# Snickerdoodle_FPGA_JA.net
KiCad netlist of a schematic drawn in Altium Designer
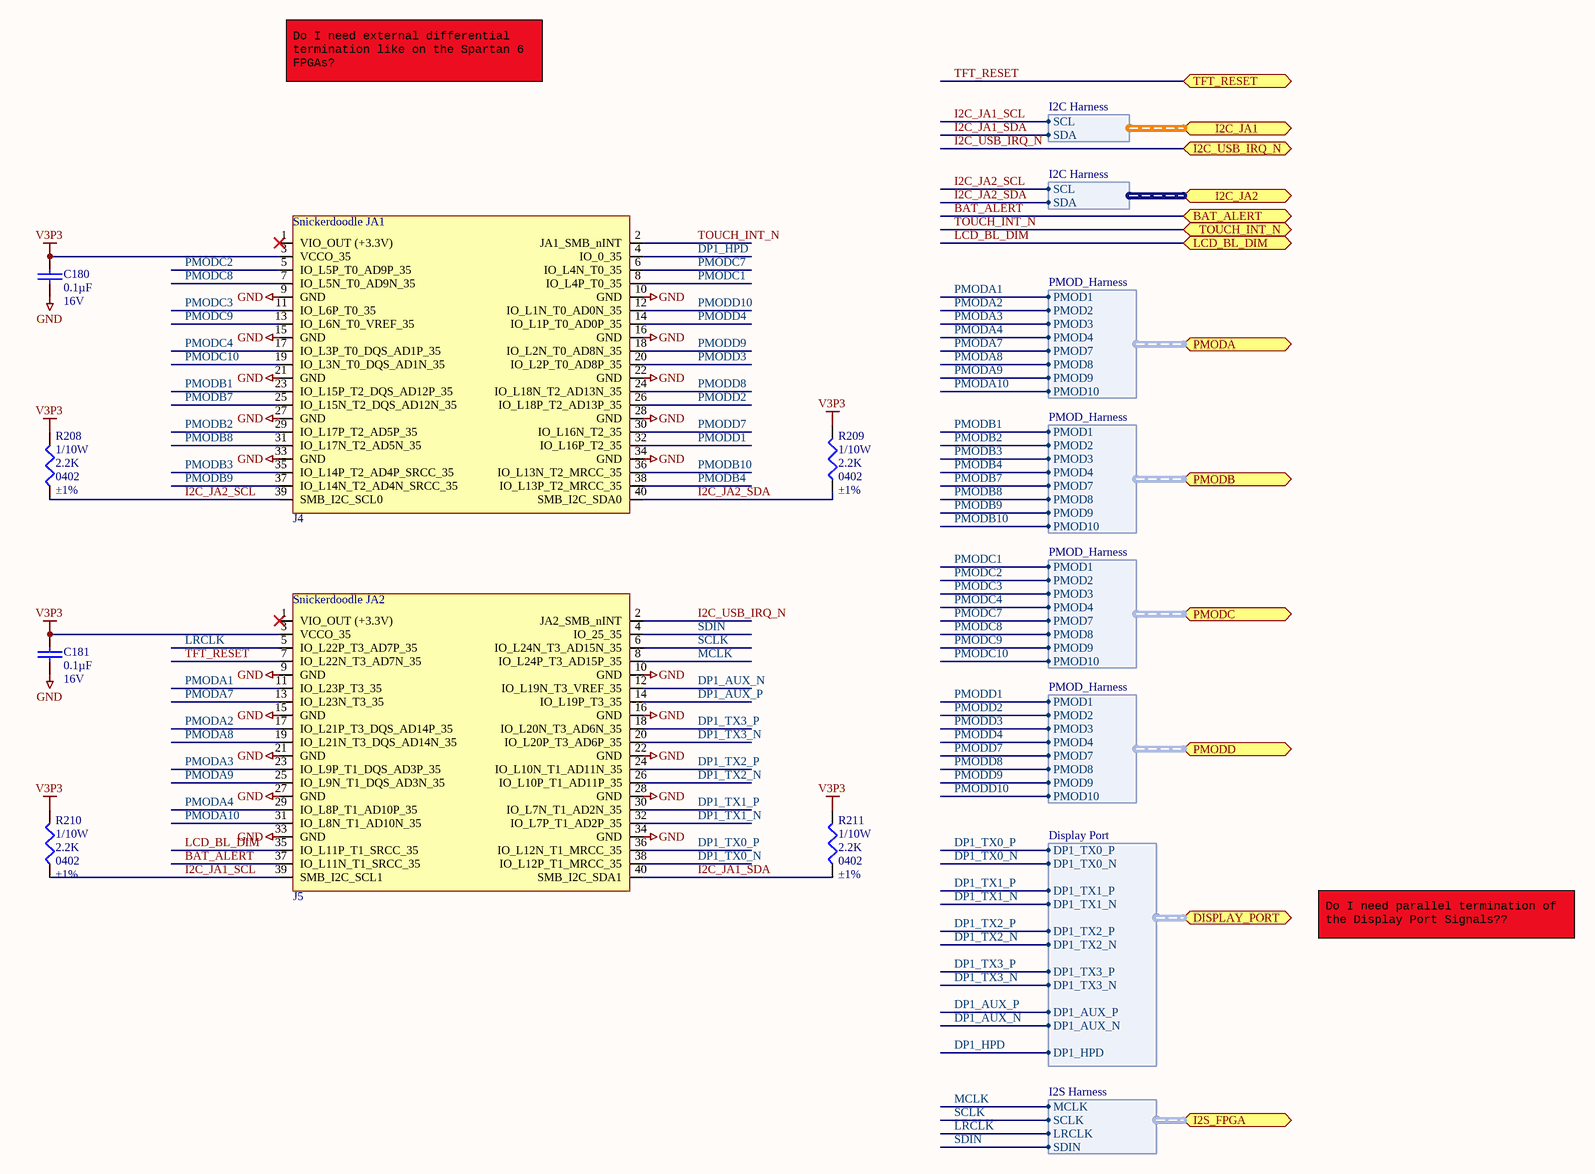
[diagram p0: Snickerdoodle FPGA JA.SchDoc]

(export (version "E")
  (design (tool "Eeschema 10.0.6"))
  (components
    (comp (ref "C180")
      (value "0.1uF")
      (footprint "C_0402")
      (description "CAP CER .10UF 16V X7R 0402")
      (fields
        (field (name "MANUFACTURER") "TDK Corporation")
        (field (name "MANUFACTURER PART NUMBER") "C1005X7R1C104K050BC")
        (field (name "CAPACITANCE") "0.1µF")
        (field (name "VOLTAGE - RATED") "16V")
      )
      (libsource (lib "Main Library") (part "C_0402_0.1UF_16V"))
    )
    (comp (ref "C181")
      (value "0.1uF")
      (footprint "C_0402")
      (description "CAP CER .10UF 16V X7R 0402")
      (fields
        (field (name "MANUFACTURER") "TDK Corporation")
        (field (name "MANUFACTURER PART NUMBER") "C1005X7R1C104K050BC")
        (field (name "CAPACITANCE") "0.1µF")
        (field (name "VOLTAGE - RATED") "16V")
      )
      (libsource (lib "Main Library") (part "C_0402_0.1UF_16V"))
    )
    (comp (ref "J4")
      (value "J_SNICKERDOODLE_JA1")
      (footprint "TFM12001-X-D-A")
      (libsource (lib "Cospan Design") (part "J_SNICKERDOODLE_JA1"))
    )
    (comp (ref "J5")
      (value "J_SNICKERDOODLE_JA2")
      (footprint "TFM12001-X-D-A")
      (libsource (lib "Cospan Design") (part "J_SNICKERDOODLE_JA2"))
    )
    (comp (ref "R208")
      (value "2.2k Ohms")
      (footprint "R_0402")
      (description "RES 2.20K OHM 1/10W 1% 0402 SMD")
      (fields
        (field (name "MANUFACTURER") "Yageo")
        (field (name "MANUFACTURER PART NUMBER") "RC0402FR-072K2L")
        (field (name "POWER (WATTS)") "1/10W")
        (field (name "RESISTANCE IN OHMS") "2.2K")
        (field (name "CASE") "0402")
        (field (name "TOLERANCE") "±1%")
      )
      (libsource (lib "Main Library") (part "R_0402_2.2K"))
    )
    (comp (ref "R209")
      (value "2.2k Ohms")
      (footprint "R_0402")
      (description "RES 2.20K OHM 1/10W 1% 0402 SMD")
      (fields
        (field (name "MANUFACTURER") "Yageo")
        (field (name "MANUFACTURER PART NUMBER") "RC0402FR-072K2L")
        (field (name "POWER (WATTS)") "1/10W")
        (field (name "RESISTANCE IN OHMS") "2.2K")
        (field (name "CASE") "0402")
        (field (name "TOLERANCE") "±1%")
      )
      (libsource (lib "Main Library") (part "R_0402_2.2K"))
    )
    (comp (ref "R210")
      (value "2.2k Ohms")
      (footprint "R_0402")
      (description "RES 2.20K OHM 1/10W 1% 0402 SMD")
      (fields
        (field (name "MANUFACTURER") "Yageo")
        (field (name "MANUFACTURER PART NUMBER") "RC0402FR-072K2L")
        (field (name "POWER (WATTS)") "1/10W")
        (field (name "RESISTANCE IN OHMS") "2.2K")
        (field (name "CASE") "0402")
        (field (name "TOLERANCE") "±1%")
      )
      (libsource (lib "Main Library") (part "R_0402_2.2K"))
    )
    (comp (ref "R211")
      (value "2.2k Ohms")
      (footprint "R_0402")
      (description "RES 2.20K OHM 1/10W 1% 0402 SMD")
      (fields
        (field (name "MANUFACTURER") "Yageo")
        (field (name "MANUFACTURER PART NUMBER") "RC0402FR-072K2L")
        (field (name "POWER (WATTS)") "1/10W")
        (field (name "RESISTANCE IN OHMS") "2.2K")
        (field (name "CASE") "0402")
        (field (name "TOLERANCE") "±1%")
      )
      (libsource (lib "Main Library") (part "R_0402_2.2K"))
    )
  )
  (nets
    (net (code "7") (name "/BAT_ALERT") (class "Default")
      (node (ref "J5") (pin "37") (pinfunction "IO_L11N_T1_SRCC_35_37") (pintype "passive"))
    )
    (net (code "8") (name "/DP1_AUX_N") (class "Default")
      (node (ref "J5") (pin "12") (pinfunction "IO_L19N_T3_VREF_35_12") (pintype "passive"))
    )
    (net (code "9") (name "/DP1_AUX_P") (class "Default")
      (node (ref "J5") (pin "14") (pinfunction "IO_L19P_T3_35_14") (pintype "passive"))
    )
    (net (code "10") (name "/DP1_HPD") (class "Default")
      (node (ref "J4") (pin "4") (pinfunction "IO_0_35_4") (pintype "passive"))
    )
    (net (code "11") (name "/DP1_TX0_N") (class "Default")
      (node (ref "J5") (pin "38") (pinfunction "IO_L12P_T1_MRCC_35_38") (pintype "passive"))
    )
    (net (code "12") (name "/DP1_TX0_P") (class "Default")
      (node (ref "J5") (pin "36") (pinfunction "IO_L12N_T1_MRCC_35_36") (pintype "passive"))
    )
    (net (code "13") (name "/DP1_TX1_N") (class "Default")
      (node (ref "J5") (pin "32") (pinfunction "IO_L7P_T1_AD2P_35_32") (pintype "passive"))
    )
    (net (code "14") (name "/DP1_TX1_P") (class "Default")
      (node (ref "J5") (pin "30") (pinfunction "IO_L7N_T1_AD2N_35_30") (pintype "passive"))
    )
    (net (code "15") (name "/DP1_TX2_N") (class "Default")
      (node (ref "J5") (pin "26") (pinfunction "IO_L10P_T1_AD11P_35_26") (pintype "passive"))
    )
    (net (code "16") (name "/DP1_TX2_P") (class "Default")
      (node (ref "J5") (pin "24") (pinfunction "IO_L10N_T1_AD11N_35_24") (pintype "passive"))
    )
    (net (code "17") (name "/DP1_TX3_N") (class "Default")
      (node (ref "J5") (pin "20") (pinfunction "IO_L20P_T3_AD6P_35_20") (pintype "passive"))
    )
    (net (code "18") (name "/DP1_TX3_P") (class "Default")
      (node (ref "J5") (pin "18") (pinfunction "IO_L20N_T3_AD6N_35_18") (pintype "passive"))
    )
    (net (code "19") (name "/I2C_JA1_SCL") (class "Default")
      (node (ref "J5") (pin "39") (pinfunction "SMB_I2C_SCL1_39") (pintype "passive"))
      (node (ref "R210") (pin "2") (pinfunction "2_2") (pintype "passive"))
    )
    (net (code "20") (name "/I2C_JA1_SDA") (class "Default")
      (node (ref "J5") (pin "40") (pinfunction "SMB_I2C_SDA1_40") (pintype "passive"))
      (node (ref "R211") (pin "2") (pinfunction "2_2") (pintype "passive"))
    )
    (net (code "21") (name "/I2C_JA2_SCL") (class "Default")
      (node (ref "J4") (pin "39") (pinfunction "SMB_I2C_SCL0_39") (pintype "passive"))
      (node (ref "R208") (pin "2") (pinfunction "2_2") (pintype "passive"))
    )
    (net (code "22") (name "/I2C_JA2_SDA") (class "Default")
      (node (ref "J4") (pin "40") (pinfunction "SMB_I2C_SDA0_40") (pintype "passive"))
      (node (ref "R209") (pin "2") (pinfunction "2_2") (pintype "passive"))
    )
    (net (code "23") (name "/I2C_USB_IRQ_N") (class "Default")
      (node (ref "J5") (pin "2") (pinfunction "JA2_SMB_nINT_2") (pintype "passive"))
    )
    (net (code "24") (name "/LCD_BL_DIM") (class "Default")
      (node (ref "J5") (pin "35") (pinfunction "IO_L11P_T1_SRCC_35_35") (pintype "passive"))
    )
    (net (code "25") (name "/LRCLK") (class "Default")
      (node (ref "J5") (pin "5") (pinfunction "IO_L22P_T3_AD7P_35_5") (pintype "passive"))
    )
    (net (code "26") (name "/MCLK") (class "Default")
      (node (ref "J5") (pin "8") (pinfunction "IO_L24P_T3_AD15P_35_8") (pintype "passive"))
    )
    (net (code "27") (name "/PMODA1") (class "Default")
      (node (ref "J5") (pin "11") (pinfunction "IO_L23P_T3_35_11") (pintype "passive"))
    )
    (net (code "28") (name "/PMODA2") (class "Default")
      (node (ref "J5") (pin "17") (pinfunction "IO_L21P_T3_DQS_AD14P_35_17") (pintype "passive"))
    )
    (net (code "29") (name "/PMODA3") (class "Default")
      (node (ref "J5") (pin "23") (pinfunction "IO_L9P_T1_DQS_AD3P_35_23") (pintype "passive"))
    )
    (net (code "30") (name "/PMODA4") (class "Default")
      (node (ref "J5") (pin "29") (pinfunction "IO_L8P_T1_AD10P_35_29") (pintype "passive"))
    )
    (net (code "31") (name "/PMODA7") (class "Default")
      (node (ref "J5") (pin "13") (pinfunction "IO_L23N_T3_35_13") (pintype "passive"))
    )
    (net (code "32") (name "/PMODA8") (class "Default")
      (node (ref "J5") (pin "19") (pinfunction "IO_L21N_T3_DQS_AD14N_35_19") (pintype "passive"))
    )
    (net (code "33") (name "/PMODA9") (class "Default")
      (node (ref "J5") (pin "25") (pinfunction "IO_L9N_T1_DQS_AD3N_35_25") (pintype "passive"))
    )
    (net (code "34") (name "/PMODA10") (class "Default")
      (node (ref "J5") (pin "31") (pinfunction "IO_L8N_T1_AD10N_35_31") (pintype "passive"))
    )
    (net (code "35") (name "/PMODB1") (class "Default")
      (node (ref "J4") (pin "23") (pinfunction "IO_L15P_T2_DQS_AD12P_35_23") (pintype "passive"))
    )
    (net (code "36") (name "/PMODB2") (class "Default")
      (node (ref "J4") (pin "29") (pinfunction "IO_L17P_T2_AD5P_35_29") (pintype "passive"))
    )
    (net (code "37") (name "/PMODB3") (class "Default")
      (node (ref "J4") (pin "35") (pinfunction "IO_L14P_T2_AD4P_SRCC_35_35") (pintype "passive"))
    )
    (net (code "38") (name "/PMODB4") (class "Default")
      (node (ref "J4") (pin "38") (pinfunction "IO_L13P_T2_MRCC_35_38") (pintype "passive"))
    )
    (net (code "39") (name "/PMODB7") (class "Default")
      (node (ref "J4") (pin "25") (pinfunction "IO_L15N_T2_DQS_AD12N_35_25") (pintype "passive"))
    )
    (net (code "40") (name "/PMODB8") (class "Default")
      (node (ref "J4") (pin "31") (pinfunction "IO_L17N_T2_AD5N_35_31") (pintype "passive"))
    )
    (net (code "41") (name "/PMODB9") (class "Default")
      (node (ref "J4") (pin "37") (pinfunction "IO_L14N_T2_AD4N_SRCC_35_37") (pintype "passive"))
    )
    (net (code "42") (name "/PMODB10") (class "Default")
      (node (ref "J4") (pin "36") (pinfunction "IO_L13N_T2_MRCC_35_36") (pintype "passive"))
    )
    (net (code "43") (name "/PMODC1") (class "Default")
      (node (ref "J4") (pin "8") (pinfunction "IO_L4P_T0_35_8") (pintype "passive"))
    )
    (net (code "44") (name "/PMODC2") (class "Default")
      (node (ref "J4") (pin "5") (pinfunction "IO_L5P_T0_AD9P_35_5") (pintype "passive"))
    )
    (net (code "45") (name "/PMODC3") (class "Default")
      (node (ref "J4") (pin "11") (pinfunction "IO_L6P_T0_35_11") (pintype "passive"))
    )
    (net (code "46") (name "/PMODC4") (class "Default")
      (node (ref "J4") (pin "17") (pinfunction "IO_L3P_T0_DQS_AD1P_35_17") (pintype "passive"))
    )
    (net (code "47") (name "/PMODC7") (class "Default")
      (node (ref "J4") (pin "6") (pinfunction "IO_L4N_T0_35_6") (pintype "passive"))
    )
    (net (code "48") (name "/PMODC8") (class "Default")
      (node (ref "J4") (pin "7") (pinfunction "IO_L5N_T0_AD9N_35_7") (pintype "passive"))
    )
    (net (code "49") (name "/PMODC9") (class "Default")
      (node (ref "J4") (pin "13") (pinfunction "IO_L6N_T0_VREF_35_13") (pintype "passive"))
    )
    (net (code "50") (name "/PMODC10") (class "Default")
      (node (ref "J4") (pin "19") (pinfunction "IO_L3N_T0_DQS_AD1N_35_19") (pintype "passive"))
    )
    (net (code "51") (name "/PMODD1") (class "Default")
      (node (ref "J4") (pin "32") (pinfunction "IO_L16P_T2_35_32") (pintype "passive"))
    )
    (net (code "52") (name "/PMODD2") (class "Default")
      (node (ref "J4") (pin "26") (pinfunction "IO_L18P_T2_AD13P_35_26") (pintype "passive"))
    )
    (net (code "53") (name "/PMODD3") (class "Default")
      (node (ref "J4") (pin "20") (pinfunction "IO_L2P_T0_AD8P_35_20") (pintype "passive"))
    )
    (net (code "54") (name "/PMODD4") (class "Default")
      (node (ref "J4") (pin "14") (pinfunction "IO_L1P_T0_AD0P_35_14") (pintype "passive"))
    )
    (net (code "55") (name "/PMODD7") (class "Default")
      (node (ref "J4") (pin "30") (pinfunction "IO_L16N_T2_35_30") (pintype "passive"))
    )
    (net (code "56") (name "/PMODD8") (class "Default")
      (node (ref "J4") (pin "24") (pinfunction "IO_L18N_T2_AD13N_35_24") (pintype "passive"))
    )
    (net (code "57") (name "/PMODD9") (class "Default")
      (node (ref "J4") (pin "18") (pinfunction "IO_L2N_T0_AD8N_35_18") (pintype "passive"))
    )
    (net (code "58") (name "/PMODD10") (class "Default")
      (node (ref "J4") (pin "12") (pinfunction "IO_L1N_T0_AD0N_35_12") (pintype "passive"))
    )
    (net (code "59") (name "/SCLK") (class "Default")
      (node (ref "J5") (pin "6") (pinfunction "IO_L24N_T3_AD15N_35_6") (pintype "passive"))
    )
    (net (code "60") (name "/SDIN") (class "Default")
      (node (ref "J5") (pin "4") (pinfunction "IO_25_35_4") (pintype "passive"))
    )
    (net (code "61") (name "/TFT_RESET") (class "Default")
      (node (ref "J5") (pin "7") (pinfunction "IO_L22N_T3_AD7N_35_7") (pintype "passive"))
    )
    (net (code "62") (name "/TOUCH_INT_N") (class "Default")
      (node (ref "J4") (pin "2") (pinfunction "JA1_SMB_nINT_2") (pintype "passive"))
    )
    (net (code "67") (name "GND") (class "Default")
      (node (ref "C180") (pin "1") (pinfunction "1_1") (pintype "passive"))
      (node (ref "C181") (pin "1") (pinfunction "1_1") (pintype "passive"))
      (node (ref "J4") (pin "10") (pinfunction "GND_10") (pintype "passive"))
      (node (ref "J4") (pin "15") (pinfunction "GND_15") (pintype "passive"))
      (node (ref "J4") (pin "16") (pinfunction "GND_16") (pintype "passive"))
      (node (ref "J4") (pin "21") (pinfunction "GND_21") (pintype "passive"))
      (node (ref "J4") (pin "22") (pinfunction "GND_22") (pintype "passive"))
      (node (ref "J4") (pin "27") (pinfunction "GND_27") (pintype "passive"))
      (node (ref "J4") (pin "28") (pinfunction "GND_28") (pintype "passive"))
      (node (ref "J4") (pin "33") (pinfunction "GND_33") (pintype "passive"))
      (node (ref "J4") (pin "34") (pinfunction "GND_34") (pintype "passive"))
      (node (ref "J4") (pin "9") (pinfunction "GND_9") (pintype "passive"))
      (node (ref "J5") (pin "10") (pinfunction "GND_10") (pintype "passive"))
      (node (ref "J5") (pin "15") (pinfunction "GND_15") (pintype "passive"))
      (node (ref "J5") (pin "16") (pinfunction "GND_16") (pintype "passive"))
      (node (ref "J5") (pin "21") (pinfunction "GND_21") (pintype "passive"))
      (node (ref "J5") (pin "22") (pinfunction "GND_22") (pintype "passive"))
      (node (ref "J5") (pin "27") (pinfunction "GND_27") (pintype "passive"))
      (node (ref "J5") (pin "28") (pinfunction "GND_28") (pintype "passive"))
      (node (ref "J5") (pin "33") (pinfunction "GND_33") (pintype "passive"))
      (node (ref "J5") (pin "34") (pinfunction "GND_34") (pintype "passive"))
      (node (ref "J5") (pin "9") (pinfunction "GND_9") (pintype "passive"))
    )
    (net (code "68") (name "V3P3") (class "Default")
      (node (ref "C180") (pin "2") (pinfunction "2_2") (pintype "passive"))
      (node (ref "C181") (pin "2") (pinfunction "2_2") (pintype "passive"))
      (node (ref "J4") (pin "3") (pinfunction "VCCO_35_3") (pintype "passive"))
      (node (ref "J5") (pin "3") (pinfunction "VCCO_35_3") (pintype "passive"))
      (node (ref "R208") (pin "1") (pinfunction "1_1") (pintype "passive"))
      (node (ref "R209") (pin "1") (pinfunction "1_1") (pintype "passive"))
      (node (ref "R210") (pin "1") (pinfunction "1_1") (pintype "passive"))
      (node (ref "R211") (pin "1") (pinfunction "1_1") (pintype "passive"))
    )
    (net (code "69") (name "unconnected-(J4-VIO_OUT_(+3.3V)-Pad1)") (class "Default")
      (node (ref "J4") (pin "1") (pinfunction "VIO_OUT_(+3.3V)_1") (pintype "passive+no_connect"))
    )
    (net (code "70") (name "unconnected-(J5-VIO_OUT_(+3.3V)-Pad1)") (class "Default")
      (node (ref "J5") (pin "1") (pinfunction "VIO_OUT_(+3.3V)_1") (pintype "passive+no_connect"))
    )
  )
)
